# Servo_Bonnet_rev_B.net
KiCad netlist of a schematic drawn in EAGLE
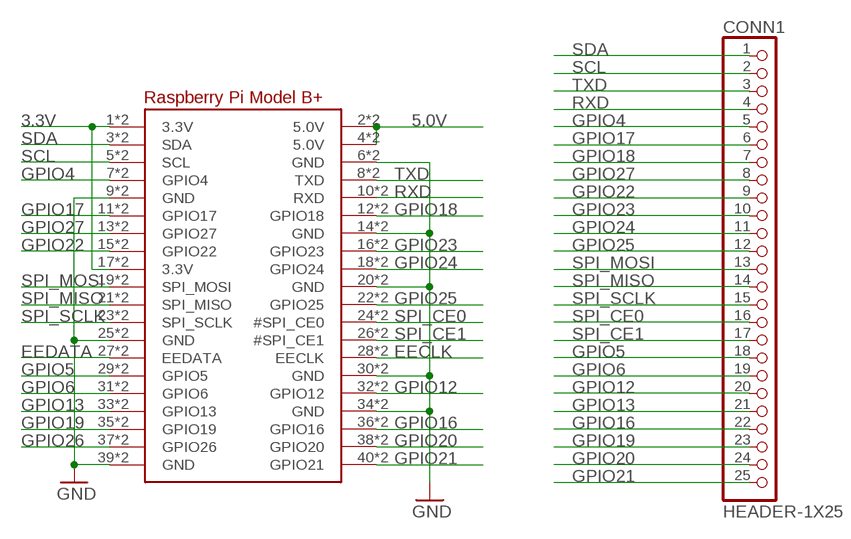
[diagram p0: schematic, sheet 1]
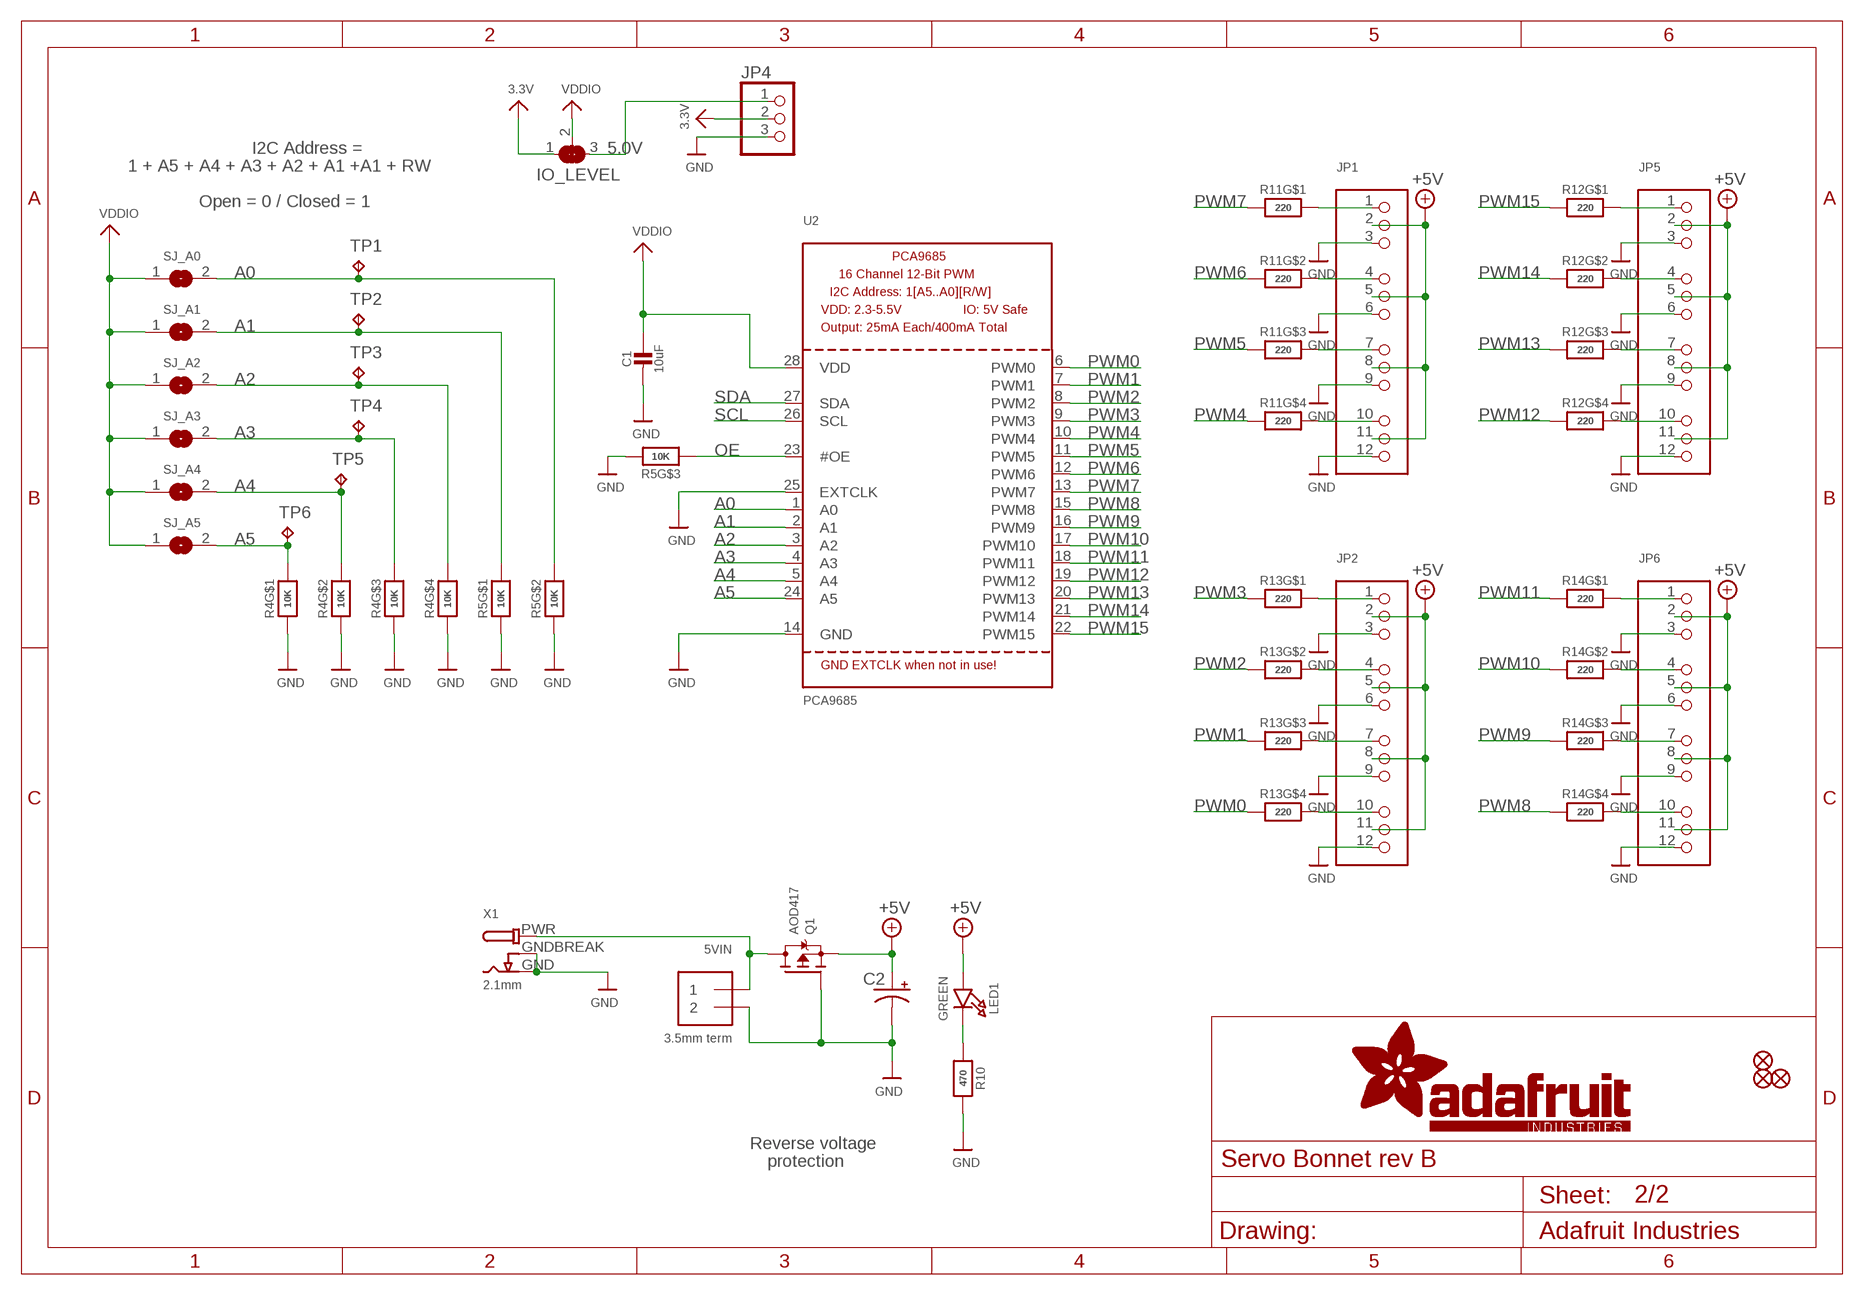
[diagram p1: schematic, sheet 2]

(export (version "E")
  (design (tool "Eeschema 10.0.6"))
  (components
    (comp (ref "CONN1")
      (value "HEADER-1X25")
      (footprint "eagle-import:1X25_ROUND_70MIL")
      (libsource (lib "eagle-import") (part "HEADER-1X25"))
    )
    (comp (ref "RPI1")
      (value "RASPBERRYPI_BPLUS_BONNET_THMSMT")
      (footprint "eagle-import:PI_BONNET_THMSMT")
      (libsource (lib "eagle-import") (part "RASPBERRYPI_BPLUS_BONNET_THMSMT"))
    )
    (comp (ref "5VIN")
      (value "3.5mm term")
      (footprint "eagle-import:TERMBLOCK_1X2-3.5MM")
      (libsource (lib "eagle-import") (part "TERMBLOCK_1X2"))
    )
    (comp (ref "C1")
      (value "10uF")
      (footprint "eagle-import:0805-NO")
      (libsource (lib "eagle-import") (part "CAP_CERAMIC0805-NOOUTLINE"))
    )
    (comp (ref "C2")
      (value "CPOL-USE3.5-8")
      (footprint "eagle-import:E3,5-8")
      (libsource (lib "eagle-import") (part "CPOL-USE3.5-8"))
    )
    (comp (ref "FID1")
      (value "FIDUCIAL_1MM")
      (footprint "eagle-import:FIDUCIAL_1MM")
      (libsource (lib "eagle-import") (part "FIDUCIAL_1MM"))
    )
    (comp (ref "FID2")
      (value "FIDUCIAL_1MM")
      (footprint "eagle-import:FIDUCIAL_1MM")
      (libsource (lib "eagle-import") (part "FIDUCIAL_1MM"))
    )
    (comp (ref "FID3")
      (value "FIDUCIAL_1MM")
      (footprint "eagle-import:FIDUCIAL_1MM")
      (fields (field (name "BOM") "EXCLUDE"))
      (libsource (lib "eagle-import") (part "FIDUCIAL_1MM"))
    )
    (comp (ref "IO_LEVEL")
      (value "SOLDERJUMPER_2WAY")
      (footprint "eagle-import:SOLDERJUMPER_2WAY_OPEN_NOPASTE")
      (libsource (lib "eagle-import") (part "SOLDERJUMPER_2WAY"))
    )
    (comp (ref "JP1")
      (value "HEADER-3X04")
      (footprint "eagle-import:3X04")
      (libsource (lib "eagle-import") (part "HEADER-3X04"))
    )
    (comp (ref "JP2")
      (value "HEADER-3X04")
      (footprint "eagle-import:3X04")
      (libsource (lib "eagle-import") (part "HEADER-3X04"))
    )
    (comp (ref "JP4")
      (value "HEADER-1X3ROUND")
      (footprint "eagle-import:1X03_ROUND")
      (libsource (lib "eagle-import") (part "HEADER-1X3ROUND"))
    )
    (comp (ref "JP5")
      (value "HEADER-3X04")
      (footprint "eagle-import:3X04")
      (libsource (lib "eagle-import") (part "HEADER-3X04"))
    )
    (comp (ref "JP6")
      (value "HEADER-3X04")
      (footprint "eagle-import:3X04")
      (libsource (lib "eagle-import") (part "HEADER-3X04"))
    )
    (comp (ref "LED1")
      (value "GREEN")
      (footprint "eagle-import:CHIPLED_0805_NOOUTLINE")
      (libsource (lib "eagle-import") (part "LED0805_NOOUTLINE"))
    )
    (comp (ref "Q1")
      (value "AOD417")
      (footprint "eagle-import:TO252")
      (libsource (lib "eagle-import") (part "MOSFET-PTO252"))
    )
    (comp (ref "R4")
      (value "10K")
      (footprint "eagle-import:RESPACK_4X0603")
      (libsource (lib "eagle-import") (part "RESISTOR_4PACK"))
    )
    (comp (ref "R5")
      (value "10K")
      (footprint "eagle-import:RESPACK_4X0603")
      (libsource (lib "eagle-import") (part "RESISTOR_4PACK"))
    )
    (comp (ref "R10")
      (value "470")
      (footprint "eagle-import:0603-NO")
      (libsource (lib "eagle-import") (part "RESISTOR_0603_NOOUT"))
    )
    (comp (ref "R11")
      (value "220")
      (footprint "eagle-import:RESPACK_4X0603")
      (libsource (lib "eagle-import") (part "RESISTOR_4PACK"))
    )
    (comp (ref "R12")
      (value "220")
      (footprint "eagle-import:RESPACK_4X0603")
      (libsource (lib "eagle-import") (part "RESISTOR_4PACK"))
    )
    (comp (ref "R13")
      (value "220")
      (footprint "eagle-import:RESPACK_4X0603")
      (libsource (lib "eagle-import") (part "RESISTOR_4PACK"))
    )
    (comp (ref "R14")
      (value "220")
      (footprint "eagle-import:RESPACK_4X0603")
      (libsource (lib "eagle-import") (part "RESISTOR_4PACK"))
    )
    (comp (ref "SJ_A0")
      (value "SOLDERJUMPERREFLOW_NOPASTE")
      (footprint "eagle-import:SOLDERJUMPER_REFLOW_NOPASTE")
      (libsource (lib "eagle-import") (part "SOLDERJUMPERREFLOW_NOPASTE"))
    )
    (comp (ref "SJ_A1")
      (value "SOLDERJUMPERREFLOW_NOPASTE")
      (footprint "eagle-import:SOLDERJUMPER_REFLOW_NOPASTE")
      (libsource (lib "eagle-import") (part "SOLDERJUMPERREFLOW_NOPASTE"))
    )
    (comp (ref "SJ_A2")
      (value "SOLDERJUMPERREFLOW_NOPASTE")
      (footprint "eagle-import:SOLDERJUMPER_REFLOW_NOPASTE")
      (libsource (lib "eagle-import") (part "SOLDERJUMPERREFLOW_NOPASTE"))
    )
    (comp (ref "SJ_A3")
      (value "SOLDERJUMPERREFLOW_NOPASTE")
      (footprint "eagle-import:SOLDERJUMPER_REFLOW_NOPASTE")
      (libsource (lib "eagle-import") (part "SOLDERJUMPERREFLOW_NOPASTE"))
    )
    (comp (ref "SJ_A4")
      (value "SOLDERJUMPERREFLOW_NOPASTE")
      (footprint "eagle-import:SOLDERJUMPER_REFLOW_NOPASTE")
      (libsource (lib "eagle-import") (part "SOLDERJUMPERREFLOW_NOPASTE"))
    )
    (comp (ref "SJ_A5")
      (value "SOLDERJUMPERREFLOW_NOPASTE")
      (footprint "eagle-import:SOLDERJUMPER_REFLOW_NOPASTE")
      (libsource (lib "eagle-import") (part "SOLDERJUMPERREFLOW_NOPASTE"))
    )
    (comp (ref "TP1")
      (value "TPB1,27")
      (footprint "eagle-import:B1,27")
      (libsource (lib "eagle-import") (part "TPB1,27"))
    )
    (comp (ref "TP2")
      (value "TPB1,27")
      (footprint "eagle-import:B1,27")
      (libsource (lib "eagle-import") (part "TPB1,27"))
    )
    (comp (ref "TP3")
      (value "TPB1,27")
      (footprint "eagle-import:B1,27")
      (libsource (lib "eagle-import") (part "TPB1,27"))
    )
    (comp (ref "TP4")
      (value "TPB1,27")
      (footprint "eagle-import:B1,27")
      (libsource (lib "eagle-import") (part "TPB1,27"))
    )
    (comp (ref "TP5")
      (value "TPB1,27")
      (footprint "eagle-import:B1,27")
      (libsource (lib "eagle-import") (part "TPB1,27"))
    )
    (comp (ref "TP6")
      (value "TPB1,27")
      (footprint "eagle-import:B1,27")
      (libsource (lib "eagle-import") (part "TPB1,27"))
    )
    (comp (ref "U2")
      (value "PCA9685")
      (footprint "eagle-import:TSSOP28")
      (libsource (lib "eagle-import") (part "PCA9685"))
    )
    (comp (ref "X1")
      (value "2.1mm")
      (footprint "eagle-import:DCJACK_2MM_PTH")
      (libsource (lib "eagle-import") (part "DCBARRELPTH"))
    )
  )
  (nets
    (net (code "1") (name "+5V") (class "Default")
      (node (ref "C2") (pin "+") (pinfunction "+_+") (pintype "passive"))
      (node (ref "JP1") (pin "11") (pinfunction "11_11") (pintype "passive"))
      (node (ref "JP1") (pin "2") (pinfunction "2_2") (pintype "passive"))
      (node (ref "JP1") (pin "5") (pinfunction "5_5") (pintype "passive"))
      (node (ref "JP1") (pin "8") (pinfunction "8_8") (pintype "passive"))
      (node (ref "JP2") (pin "11") (pinfunction "11_11") (pintype "passive"))
      (node (ref "JP2") (pin "2") (pinfunction "2_2") (pintype "passive"))
      (node (ref "JP2") (pin "5") (pinfunction "5_5") (pintype "passive"))
      (node (ref "JP2") (pin "8") (pinfunction "8_8") (pintype "passive"))
      (node (ref "JP5") (pin "11") (pinfunction "11_11") (pintype "passive"))
      (node (ref "JP5") (pin "2") (pinfunction "2_2") (pintype "passive"))
      (node (ref "JP5") (pin "5") (pinfunction "5_5") (pintype "passive"))
      (node (ref "JP5") (pin "8") (pinfunction "8_8") (pintype "passive"))
      (node (ref "JP6") (pin "11") (pinfunction "11_11") (pintype "passive"))
      (node (ref "JP6") (pin "2") (pinfunction "2_2") (pintype "passive"))
      (node (ref "JP6") (pin "5") (pinfunction "5_5") (pintype "passive"))
      (node (ref "JP6") (pin "8") (pinfunction "8_8") (pintype "passive"))
      (node (ref "LED1") (pin "A") (pinfunction "A_A") (pintype "passive"))
      (node (ref "Q1") (pin "2") (pinfunction "S_2") (pintype "passive"))
    )
    (net (code "2") (name "3.3V") (class "Default")
      (node (ref "IO_LEVEL") (pin "1") (pinfunction "1_1") (pintype "passive"))
      (node (ref "JP4") (pin "2") (pinfunction "2_2") (pintype "passive"))
      (node (ref "RPI1") (pin "1") (pinfunction "3.3V_1") (pintype "power_in"))
      (node (ref "RPI1") (pin "17") (pinfunction "3.3V_17") (pintype "power_in"))
      (node (ref "RPI1") (pin "S1") (pinfunction "3.3V_S1") (pintype "power_in"))
      (node (ref "RPI1") (pin "S17") (pinfunction "3.3V_S17") (pintype "power_in"))
    )
    (net (code "3") (name "5.0V") (class "Default")
      (node (ref "IO_LEVEL") (pin "3") (pinfunction "3_3") (pintype "passive"))
      (node (ref "JP4") (pin "1") (pinfunction "1_1") (pintype "passive"))
      (node (ref "RPI1") (pin "2") (pinfunction "5.0V_2") (pintype "power_in"))
      (node (ref "RPI1") (pin "4") (pinfunction "5.0V_4") (pintype "power_in"))
      (node (ref "RPI1") (pin "S2") (pinfunction "5.0V_S2") (pintype "power_in"))
      (node (ref "RPI1") (pin "S4") (pinfunction "5.0V_S4") (pintype "power_in"))
    )
    (net (code "4") (name "A0") (class "Default")
      (node (ref "R5") (pin "7") (pinfunction "2_7") (pintype "passive"))
      (node (ref "SJ_A0") (pin "2") (pinfunction "2_2") (pintype "passive"))
      (node (ref "TP1") (pin "TP") (pinfunction "TP_TP") (pintype "input"))
      (node (ref "U2") (pin "1") (pinfunction "A0_1") (pintype "bidirectional"))
    )
    (net (code "5") (name "A1") (class "Default")
      (node (ref "R5") (pin "8") (pinfunction "2_8") (pintype "passive"))
      (node (ref "SJ_A1") (pin "2") (pinfunction "2_2") (pintype "passive"))
      (node (ref "TP2") (pin "TP") (pinfunction "TP_TP") (pintype "input"))
      (node (ref "U2") (pin "2") (pinfunction "A1_2") (pintype "bidirectional"))
    )
    (net (code "6") (name "A2") (class "Default")
      (node (ref "R4") (pin "5") (pinfunction "2_5") (pintype "passive"))
      (node (ref "SJ_A2") (pin "2") (pinfunction "2_2") (pintype "passive"))
      (node (ref "TP3") (pin "TP") (pinfunction "TP_TP") (pintype "input"))
      (node (ref "U2") (pin "3") (pinfunction "A2_3") (pintype "bidirectional"))
    )
    (net (code "7") (name "A3") (class "Default")
      (node (ref "R4") (pin "6") (pinfunction "2_6") (pintype "passive"))
      (node (ref "SJ_A3") (pin "2") (pinfunction "2_2") (pintype "passive"))
      (node (ref "TP4") (pin "TP") (pinfunction "TP_TP") (pintype "input"))
      (node (ref "U2") (pin "4") (pinfunction "A3_4") (pintype "bidirectional"))
    )
    (net (code "8") (name "A4") (class "Default")
      (node (ref "R4") (pin "7") (pinfunction "2_7") (pintype "passive"))
      (node (ref "SJ_A4") (pin "2") (pinfunction "2_2") (pintype "passive"))
      (node (ref "TP5") (pin "TP") (pinfunction "TP_TP") (pintype "input"))
      (node (ref "U2") (pin "5") (pinfunction "A4_5") (pintype "bidirectional"))
    )
    (net (code "9") (name "A5") (class "Default")
      (node (ref "R4") (pin "8") (pinfunction "2_8") (pintype "passive"))
      (node (ref "SJ_A5") (pin "2") (pinfunction "2_2") (pintype "passive"))
      (node (ref "TP6") (pin "TP") (pinfunction "TP_TP") (pintype "input"))
      (node (ref "U2") (pin "24") (pinfunction "A5_24") (pintype "bidirectional"))
    )
    (net (code "10") (name "EECLK") (class "Default")
      (node (ref "RPI1") (pin "28") (pinfunction "EECLK_28") (pintype "bidirectional"))
      (node (ref "RPI1") (pin "S28") (pinfunction "EECLK_S28") (pintype "bidirectional"))
    )
    (net (code "11") (name "EEDATA") (class "Default")
      (node (ref "RPI1") (pin "27") (pinfunction "EEDATA_27") (pintype "bidirectional"))
      (node (ref "RPI1") (pin "S27") (pinfunction "EEDATA_S27") (pintype "bidirectional"))
    )
    (net (code "12") (name "GND") (class "Default")
      (node (ref "5VIN") (pin "2") (pinfunction "2_2") (pintype "passive"))
      (node (ref "C1") (pin "2") (pinfunction "2_2") (pintype "passive"))
      (node (ref "C2") (pin "-") (pinfunction "-_-") (pintype "passive"))
      (node (ref "JP1") (pin "12") (pinfunction "12_12") (pintype "passive"))
      (node (ref "JP1") (pin "3") (pinfunction "3_3") (pintype "passive"))
      (node (ref "JP1") (pin "6") (pinfunction "6_6") (pintype "passive"))
      (node (ref "JP1") (pin "9") (pinfunction "9_9") (pintype "passive"))
      (node (ref "JP2") (pin "12") (pinfunction "12_12") (pintype "passive"))
      (node (ref "JP2") (pin "3") (pinfunction "3_3") (pintype "passive"))
      (node (ref "JP2") (pin "6") (pinfunction "6_6") (pintype "passive"))
      (node (ref "JP2") (pin "9") (pinfunction "9_9") (pintype "passive"))
      (node (ref "JP4") (pin "3") (pinfunction "3_3") (pintype "passive"))
      (node (ref "JP5") (pin "12") (pinfunction "12_12") (pintype "passive"))
      (node (ref "JP5") (pin "3") (pinfunction "3_3") (pintype "passive"))
      (node (ref "JP5") (pin "6") (pinfunction "6_6") (pintype "passive"))
      (node (ref "JP5") (pin "9") (pinfunction "9_9") (pintype "passive"))
      (node (ref "JP6") (pin "12") (pinfunction "12_12") (pintype "passive"))
      (node (ref "JP6") (pin "3") (pinfunction "3_3") (pintype "passive"))
      (node (ref "JP6") (pin "6") (pinfunction "6_6") (pintype "passive"))
      (node (ref "JP6") (pin "9") (pinfunction "9_9") (pintype "passive"))
      (node (ref "Q1") (pin "1") (pinfunction "G_1") (pintype "passive"))
      (node (ref "R10") (pin "2") (pinfunction "2_2") (pintype "passive"))
      (node (ref "R4") (pin "1") (pinfunction "1_1") (pintype "passive"))
      (node (ref "R4") (pin "2") (pinfunction "1_2") (pintype "passive"))
      (node (ref "R4") (pin "3") (pinfunction "1_3") (pintype "passive"))
      (node (ref "R4") (pin "4") (pinfunction "1_4") (pintype "passive"))
      (node (ref "R5") (pin "1") (pinfunction "1_1") (pintype "passive"))
      (node (ref "R5") (pin "2") (pinfunction "1_2") (pintype "passive"))
      (node (ref "R5") (pin "6") (pinfunction "2_6") (pintype "passive"))
      (node (ref "RPI1") (pin "14") (pinfunction "GND_14") (pintype "power_in"))
      (node (ref "RPI1") (pin "20") (pinfunction "GND_20") (pintype "power_in"))
      (node (ref "RPI1") (pin "25") (pinfunction "GND_25") (pintype "power_in"))
      (node (ref "RPI1") (pin "30") (pinfunction "GND_30") (pintype "power_in"))
      (node (ref "RPI1") (pin "34") (pinfunction "GND_34") (pintype "power_in"))
      (node (ref "RPI1") (pin "39") (pinfunction "GND_39") (pintype "power_in"))
      (node (ref "RPI1") (pin "6") (pinfunction "GND_6") (pintype "power_in"))
      (node (ref "RPI1") (pin "9") (pinfunction "GND_9") (pintype "power_in"))
      (node (ref "RPI1") (pin "S14") (pinfunction "GND_S14") (pintype "power_in"))
      (node (ref "RPI1") (pin "S20") (pinfunction "GND_S20") (pintype "power_in"))
      (node (ref "RPI1") (pin "S25") (pinfunction "GND_S25") (pintype "power_in"))
      (node (ref "RPI1") (pin "S30") (pinfunction "GND_S30") (pintype "power_in"))
      (node (ref "RPI1") (pin "S34") (pinfunction "GND_S34") (pintype "power_in"))
      (node (ref "RPI1") (pin "S39") (pinfunction "GND_S39") (pintype "power_in"))
      (node (ref "RPI1") (pin "S6") (pinfunction "GND_S6") (pintype "power_in"))
      (node (ref "RPI1") (pin "S9") (pinfunction "GND_S9") (pintype "power_in"))
      (node (ref "U2") (pin "14") (pinfunction "GND_14") (pintype "power_in"))
      (node (ref "U2") (pin "25") (pinfunction "EXTCLK_25") (pintype "input"))
      (node (ref "X1") (pin "GND") (pinfunction "GND_GND") (pintype "power_in"))
      (node (ref "X1") (pin "GNDBREAK") (pinfunction "GNDBREAK_GNDBREAK") (pintype "power_in"))
    )
    (net (code "13") (name "GPIO4") (class "Default")
      (node (ref "CONN1") (pin "5") (pinfunction "5_5") (pintype "passive"))
      (node (ref "RPI1") (pin "7") (pinfunction "GPIO4_7") (pintype "bidirectional"))
      (node (ref "RPI1") (pin "S7") (pinfunction "GPIO4_S7") (pintype "bidirectional"))
    )
    (net (code "14") (name "GPIO5") (class "Default")
      (node (ref "CONN1") (pin "18") (pinfunction "18_18") (pintype "passive"))
      (node (ref "RPI1") (pin "29") (pinfunction "GPIO5_29") (pintype "bidirectional"))
      (node (ref "RPI1") (pin "S29") (pinfunction "GPIO5_S29") (pintype "bidirectional"))
    )
    (net (code "15") (name "GPIO6") (class "Default")
      (node (ref "CONN1") (pin "19") (pinfunction "19_19") (pintype "passive"))
      (node (ref "RPI1") (pin "31") (pinfunction "GPIO6_31") (pintype "bidirectional"))
      (node (ref "RPI1") (pin "S31") (pinfunction "GPIO6_S31") (pintype "bidirectional"))
    )
    (net (code "16") (name "GPIO12") (class "Default")
      (node (ref "CONN1") (pin "20") (pinfunction "20_20") (pintype "passive"))
      (node (ref "RPI1") (pin "32") (pinfunction "GPIO12_32") (pintype "bidirectional"))
      (node (ref "RPI1") (pin "S32") (pinfunction "GPIO12_S32") (pintype "bidirectional"))
    )
    (net (code "17") (name "GPIO13") (class "Default")
      (node (ref "CONN1") (pin "21") (pinfunction "21_21") (pintype "passive"))
      (node (ref "RPI1") (pin "33") (pinfunction "GPIO13_33") (pintype "bidirectional"))
      (node (ref "RPI1") (pin "S33") (pinfunction "GPIO13_S33") (pintype "bidirectional"))
    )
    (net (code "18") (name "GPIO16") (class "Default")
      (node (ref "CONN1") (pin "22") (pinfunction "22_22") (pintype "passive"))
      (node (ref "RPI1") (pin "36") (pinfunction "GPIO16_36") (pintype "bidirectional"))
      (node (ref "RPI1") (pin "S36") (pinfunction "GPIO16_S36") (pintype "bidirectional"))
    )
    (net (code "19") (name "GPIO17") (class "Default")
      (node (ref "CONN1") (pin "6") (pinfunction "6_6") (pintype "passive"))
      (node (ref "RPI1") (pin "11") (pinfunction "GPIO17_11") (pintype "bidirectional"))
      (node (ref "RPI1") (pin "S11") (pinfunction "GPIO17_S11") (pintype "bidirectional"))
    )
    (net (code "20") (name "GPIO18") (class "Default")
      (node (ref "CONN1") (pin "7") (pinfunction "7_7") (pintype "passive"))
      (node (ref "RPI1") (pin "12") (pinfunction "GPIO18_12") (pintype "bidirectional"))
      (node (ref "RPI1") (pin "S12") (pinfunction "GPIO18_S12") (pintype "bidirectional"))
    )
    (net (code "21") (name "GPIO19") (class "Default")
      (node (ref "CONN1") (pin "23") (pinfunction "23_23") (pintype "passive"))
      (node (ref "RPI1") (pin "35") (pinfunction "GPIO19_35") (pintype "bidirectional"))
      (node (ref "RPI1") (pin "S35") (pinfunction "GPIO19_S35") (pintype "bidirectional"))
    )
    (net (code "22") (name "GPIO20") (class "Default")
      (node (ref "CONN1") (pin "24") (pinfunction "24_24") (pintype "passive"))
      (node (ref "RPI1") (pin "38") (pinfunction "GPIO20_38") (pintype "bidirectional"))
      (node (ref "RPI1") (pin "S38") (pinfunction "GPIO20_S38") (pintype "bidirectional"))
    )
    (net (code "23") (name "GPIO21") (class "Default")
      (node (ref "CONN1") (pin "25") (pinfunction "25_25") (pintype "passive"))
      (node (ref "RPI1") (pin "40") (pinfunction "GPIO21_40") (pintype "bidirectional"))
      (node (ref "RPI1") (pin "S40") (pinfunction "GPIO21_S40") (pintype "bidirectional"))
    )
    (net (code "24") (name "GPIO22") (class "Default")
      (node (ref "CONN1") (pin "9") (pinfunction "9_9") (pintype "passive"))
      (node (ref "RPI1") (pin "15") (pinfunction "GPIO22_15") (pintype "bidirectional"))
      (node (ref "RPI1") (pin "S15") (pinfunction "GPIO22_S15") (pintype "bidirectional"))
    )
    (net (code "25") (name "GPIO23") (class "Default")
      (node (ref "CONN1") (pin "10") (pinfunction "10_10") (pintype "passive"))
      (node (ref "RPI1") (pin "16") (pinfunction "GPIO23_16") (pintype "bidirectional"))
      (node (ref "RPI1") (pin "S16") (pinfunction "GPIO23_S16") (pintype "bidirectional"))
    )
    (net (code "26") (name "GPIO24") (class "Default")
      (node (ref "CONN1") (pin "11") (pinfunction "11_11") (pintype "passive"))
      (node (ref "RPI1") (pin "18") (pinfunction "GPIO24_18") (pintype "bidirectional"))
      (node (ref "RPI1") (pin "S18") (pinfunction "GPIO24_S18") (pintype "bidirectional"))
    )
    (net (code "27") (name "GPIO25") (class "Default")
      (node (ref "CONN1") (pin "12") (pinfunction "12_12") (pintype "passive"))
      (node (ref "RPI1") (pin "22") (pinfunction "GPIO25_22") (pintype "bidirectional"))
      (node (ref "RPI1") (pin "S22") (pinfunction "GPIO25_S22") (pintype "bidirectional"))
    )
    (net (code "28") (name "GPIO26") (class "Default")
      (node (ref "RPI1") (pin "37") (pinfunction "GPIO26_37") (pintype "bidirectional"))
      (node (ref "RPI1") (pin "S37") (pinfunction "GPIO26_S37") (pintype "bidirectional"))
    )
    (net (code "29") (name "GPIO27") (class "Default")
      (node (ref "CONN1") (pin "8") (pinfunction "8_8") (pintype "passive"))
      (node (ref "RPI1") (pin "13") (pinfunction "GPIO27_13") (pintype "bidirectional"))
      (node (ref "RPI1") (pin "S13") (pinfunction "GPIO27_S13") (pintype "bidirectional"))
    )
    (net (code "30") (name "Net-(LED1-PadC)") (class "Default")
      (node (ref "LED1") (pin "C") (pinfunction "C_C") (pintype "passive"))
      (node (ref "R10") (pin "1") (pinfunction "1_1") (pintype "passive"))
    )
    (net (code "31") (name "Net-(Q1-D)") (class "Default")
      (node (ref "5VIN") (pin "1") (pinfunction "1_1") (pintype "passive"))
      (node (ref "Q1") (pin "3") (pinfunction "D_3") (pintype "passive"))
      (node (ref "X1") (pin "PWR") (pinfunction "PWR_PWR") (pintype "power_in"))
    )
    (net (code "32") (name "Net-(R11A-2)") (class "Default")
      (node (ref "JP1") (pin "1") (pinfunction "1_1") (pintype "passive"))
      (node (ref "R11") (pin "8") (pinfunction "2_8") (pintype "passive"))
    )
    (net (code "33") (name "Net-(R11B-2)") (class "Default")
      (node (ref "JP1") (pin "4") (pinfunction "4_4") (pintype "passive"))
      (node (ref "R11") (pin "7") (pinfunction "2_7") (pintype "passive"))
    )
    (net (code "34") (name "Net-(R11C-2)") (class "Default")
      (node (ref "JP1") (pin "7") (pinfunction "7_7") (pintype "passive"))
      (node (ref "R11") (pin "6") (pinfunction "2_6") (pintype "passive"))
    )
    (net (code "35") (name "Net-(R11D-2)") (class "Default")
      (node (ref "JP1") (pin "10") (pinfunction "10_10") (pintype "passive"))
      (node (ref "R11") (pin "5") (pinfunction "2_5") (pintype "passive"))
    )
    (net (code "36") (name "Net-(R12A-2)") (class "Default")
      (node (ref "JP5") (pin "1") (pinfunction "1_1") (pintype "passive"))
      (node (ref "R12") (pin "8") (pinfunction "2_8") (pintype "passive"))
    )
    (net (code "37") (name "Net-(R12B-2)") (class "Default")
      (node (ref "JP5") (pin "4") (pinfunction "4_4") (pintype "passive"))
      (node (ref "R12") (pin "7") (pinfunction "2_7") (pintype "passive"))
    )
    (net (code "38") (name "Net-(R12C-2)") (class "Default")
      (node (ref "JP5") (pin "7") (pinfunction "7_7") (pintype "passive"))
      (node (ref "R12") (pin "6") (pinfunction "2_6") (pintype "passive"))
    )
    (net (code "39") (name "Net-(R12D-2)") (class "Default")
      (node (ref "JP5") (pin "10") (pinfunction "10_10") (pintype "passive"))
      (node (ref "R12") (pin "5") (pinfunction "2_5") (pintype "passive"))
    )
    (net (code "40") (name "Net-(R13A-2)") (class "Default")
      (node (ref "JP2") (pin "1") (pinfunction "1_1") (pintype "passive"))
      (node (ref "R13") (pin "8") (pinfunction "2_8") (pintype "passive"))
    )
    (net (code "41") (name "Net-(R13B-2)") (class "Default")
      (node (ref "JP2") (pin "4") (pinfunction "4_4") (pintype "passive"))
      (node (ref "R13") (pin "7") (pinfunction "2_7") (pintype "passive"))
    )
    (net (code "42") (name "Net-(R13C-2)") (class "Default")
      (node (ref "JP2") (pin "7") (pinfunction "7_7") (pintype "passive"))
      (node (ref "R13") (pin "6") (pinfunction "2_6") (pintype "passive"))
    )
    (net (code "43") (name "Net-(R13D-2)") (class "Default")
      (node (ref "JP2") (pin "10") (pinfunction "10_10") (pintype "passive"))
      (node (ref "R13") (pin "5") (pinfunction "2_5") (pintype "passive"))
    )
    (net (code "44") (name "Net-(R14A-2)") (class "Default")
      (node (ref "JP6") (pin "1") (pinfunction "1_1") (pintype "passive"))
      (node (ref "R14") (pin "8") (pinfunction "2_8") (pintype "passive"))
    )
    (net (code "45") (name "Net-(R14B-2)") (class "Default")
      (node (ref "JP6") (pin "4") (pinfunction "4_4") (pintype "passive"))
      (node (ref "R14") (pin "7") (pinfunction "2_7") (pintype "passive"))
    )
    (net (code "46") (name "Net-(R14C-2)") (class "Default")
      (node (ref "JP6") (pin "7") (pinfunction "7_7") (pintype "passive"))
      (node (ref "R14") (pin "6") (pinfunction "2_6") (pintype "passive"))
    )
    (net (code "47") (name "Net-(R14D-2)") (class "Default")
      (node (ref "JP6") (pin "10") (pinfunction "10_10") (pintype "passive"))
      (node (ref "R14") (pin "5") (pinfunction "2_5") (pintype "passive"))
    )
    (net (code "48") (name "OE") (class "Default")
      (node (ref "R5") (pin "3") (pinfunction "1_3") (pintype "passive"))
      (node (ref "U2") (pin "23") (pinfunction "#OE_23") (pintype "input"))
    )
    (net (code "49") (name "PWM0") (class "Default")
      (node (ref "R13") (pin "4") (pinfunction "1_4") (pintype "passive"))
      (node (ref "U2") (pin "6") (pinfunction "PWM0_6") (pintype "output"))
    )
    (net (code "50") (name "PWM1") (class "Default")
      (node (ref "R13") (pin "3") (pinfunction "1_3") (pintype "passive"))
      (node (ref "U2") (pin "7") (pinfunction "PWM1_7") (pintype "output"))
    )
    (net (code "51") (name "PWM2") (class "Default")
      (node (ref "R13") (pin "2") (pinfunction "1_2") (pintype "passive"))
      (node (ref "U2") (pin "8") (pinfunction "PWM2_8") (pintype "output"))
    )
    (net (code "52") (name "PWM3") (class "Default")
      (node (ref "R13") (pin "1") (pinfunction "1_1") (pintype "passive"))
      (node (ref "U2") (pin "9") (pinfunction "PWM3_9") (pintype "output"))
    )
    (net (code "53") (name "PWM4") (class "Default")
      (node (ref "R11") (pin "4") (pinfunction "1_4") (pintype "passive"))
      (node (ref "U2") (pin "10") (pinfunction "PWM4_10") (pintype "output"))
    )
    (net (code "54") (name "PWM5") (class "Default")
      (node (ref "R11") (pin "3") (pinfunction "1_3") (pintype "passive"))
      (node (ref "U2") (pin "11") (pinfunction "PWM5_11") (pintype "output"))
    )
    (net (code "55") (name "PWM6") (class "Default")
      (node (ref "R11") (pin "2") (pinfunction "1_2") (pintype "passive"))
      (node (ref "U2") (pin "12") (pinfunction "PWM6_12") (pintype "output"))
    )
    (net (code "56") (name "PWM7") (class "Default")
      (node (ref "R11") (pin "1") (pinfunction "1_1") (pintype "passive"))
      (node (ref "U2") (pin "13") (pinfunction "PWM7_13") (pintype "output"))
    )
    (net (code "57") (name "PWM8") (class "Default")
      (node (ref "R14") (pin "4") (pinfunction "1_4") (pintype "passive"))
      (node (ref "U2") (pin "15") (pinfunction "PWM8_15") (pintype "output"))
    )
    (net (code "58") (name "PWM9") (class "Default")
      (node (ref "R14") (pin "3") (pinfunction "1_3") (pintype "passive"))
      (node (ref "U2") (pin "16") (pinfunction "PWM9_16") (pintype "output"))
    )
    (net (code "59") (name "PWM10") (class "Default")
      (node (ref "R14") (pin "2") (pinfunction "1_2") (pintype "passive"))
      (node (ref "U2") (pin "17") (pinfunction "PWM10_17") (pintype "output"))
    )
    (net (code "60") (name "PWM11") (class "Default")
      (node (ref "R14") (pin "1") (pinfunction "1_1") (pintype "passive"))
      (node (ref "U2") (pin "18") (pinfunction "PWM11_18") (pintype "output"))
    )
    (net (code "61") (name "PWM12") (class "Default")
      (node (ref "R12") (pin "4") (pinfunction "1_4") (pintype "passive"))
      (node (ref "U2") (pin "19") (pinfunction "PWM12_19") (pintype "output"))
    )
    (net (code "62") (name "PWM13") (class "Default")
      (node (ref "R12") (pin "3") (pinfunction "1_3") (pintype "passive"))
      (node (ref "U2") (pin "20") (pinfunction "PWM13_20") (pintype "output"))
    )
    (net (code "63") (name "PWM14") (class "Default")
      (node (ref "R12") (pin "2") (pinfunction "1_2") (pintype "passive"))
      (node (ref "U2") (pin "21") (pinfunction "PWM14_21") (pintype "output"))
    )
    (net (code "64") (name "PWM15") (class "Default")
      (node (ref "R12") (pin "1") (pinfunction "1_1") (pintype "passive"))
      (node (ref "U2") (pin "22") (pinfunction "PWM15_22") (pintype "output"))
    )
    (net (code "65") (name "RXD") (class "Default")
      (node (ref "CONN1") (pin "4") (pinfunction "4_4") (pintype "passive"))
      (node (ref "RPI1") (pin "10") (pinfunction "RXD_10") (pintype "bidirectional"))
      (node (ref "RPI1") (pin "S10") (pinfunction "RXD_S10") (pintype "bidirectional"))
    )
    (net (code "66") (name "SCL") (class "Default")
      (node (ref "CONN1") (pin "2") (pinfunction "2_2") (pintype "passive"))
      (node (ref "RPI1") (pin "5") (pinfunction "SCL_5") (pintype "bidirectional"))
      (node (ref "RPI1") (pin "S5") (pinfunction "SCL_S5") (pintype "bidirectional"))
      (node (ref "U2") (pin "26") (pinfunction "SCL_26") (pintype "bidirectional"))
    )
    (net (code "67") (name "SDA") (class "Default")
      (node (ref "CONN1") (pin "1") (pinfunction "1_1") (pintype "passive"))
      (node (ref "RPI1") (pin "3") (pinfunction "SDA_3") (pintype "bidirectional"))
      (node (ref "RPI1") (pin "S3") (pinfunction "SDA_S3") (pintype "bidirectional"))
      (node (ref "U2") (pin "27") (pinfunction "SDA_27") (pintype "bidirectional"))
    )
    (net (code "68") (name "SPI_CE0") (class "Default")
      (node (ref "CONN1") (pin "16") (pinfunction "16_16") (pintype "passive"))
      (node (ref "RPI1") (pin "24") (pinfunction "#SPI_CE0_24") (pintype "bidirectional"))
      (node (ref "RPI1") (pin "S24") (pinfunction "#SPI_CE0_S24") (pintype "bidirectional"))
    )
    (net (code "69") (name "SPI_CE1") (class "Default")
      (node (ref "CONN1") (pin "17") (pinfunction "17_17") (pintype "passive"))
      (node (ref "RPI1") (pin "26") (pinfunction "#SPI_CE1_26") (pintype "bidirectional"))
      (node (ref "RPI1") (pin "S26") (pinfunction "#SPI_CE1_S26") (pintype "bidirectional"))
    )
    (net (code "70") (name "SPI_MISO") (class "Default")
      (node (ref "CONN1") (pin "14") (pinfunction "14_14") (pintype "passive"))
      (node (ref "RPI1") (pin "21") (pinfunction "SPI_MISO_21") (pintype "bidirectional"))
      (node (ref "RPI1") (pin "S21") (pinfunction "SPI_MISO_S21") (pintype "bidirectional"))
    )
    (net (code "71") (name "SPI_MOSI") (class "Default")
      (node (ref "CONN1") (pin "13") (pinfunction "13_13") (pintype "passive"))
      (node (ref "RPI1") (pin "19") (pinfunction "SPI_MOSI_19") (pintype "bidirectional"))
      (node (ref "RPI1") (pin "S19") (pinfunction "SPI_MOSI_S19") (pintype "bidirectional"))
    )
    (net (code "72") (name "SPI_SCLK") (class "Default")
      (node (ref "CONN1") (pin "15") (pinfunction "15_15") (pintype "passive"))
      (node (ref "RPI1") (pin "23") (pinfunction "SPI_SCLK_23") (pintype "bidirectional"))
      (node (ref "RPI1") (pin "S23") (pinfunction "SPI_SCLK_S23") (pintype "bidirectional"))
    )
    (net (code "73") (name "TXD") (class "Default")
      (node (ref "CONN1") (pin "3") (pinfunction "3_3") (pintype "passive"))
      (node (ref "RPI1") (pin "8") (pinfunction "TXD_8") (pintype "bidirectional"))
      (node (ref "RPI1") (pin "S8") (pinfunction "TXD_S8") (pintype "bidirectional"))
    )
    (net (code "74") (name "VDDIO") (class "Default")
      (node (ref "C1") (pin "1") (pinfunction "1_1") (pintype "passive"))
      (node (ref "IO_LEVEL") (pin "2") (pinfunction "2_2") (pintype "passive"))
      (node (ref "SJ_A0") (pin "1") (pinfunction "1_1") (pintype "passive"))
      (node (ref "SJ_A1") (pin "1") (pinfunction "1_1") (pintype "passive"))
      (node (ref "SJ_A2") (pin "1") (pinfunction "1_1") (pintype "passive"))
      (node (ref "SJ_A3") (pin "1") (pinfunction "1_1") (pintype "passive"))
      (node (ref "SJ_A4") (pin "1") (pinfunction "1_1") (pintype "passive"))
      (node (ref "SJ_A5") (pin "1") (pinfunction "1_1") (pintype "passive"))
      (node (ref "U2") (pin "28") (pinfunction "VDD_28") (pintype "power_in"))
    )
  )
)
